# schematic_breakout_pcb.net
KiCad netlist of a schematic drawn in EAGLE
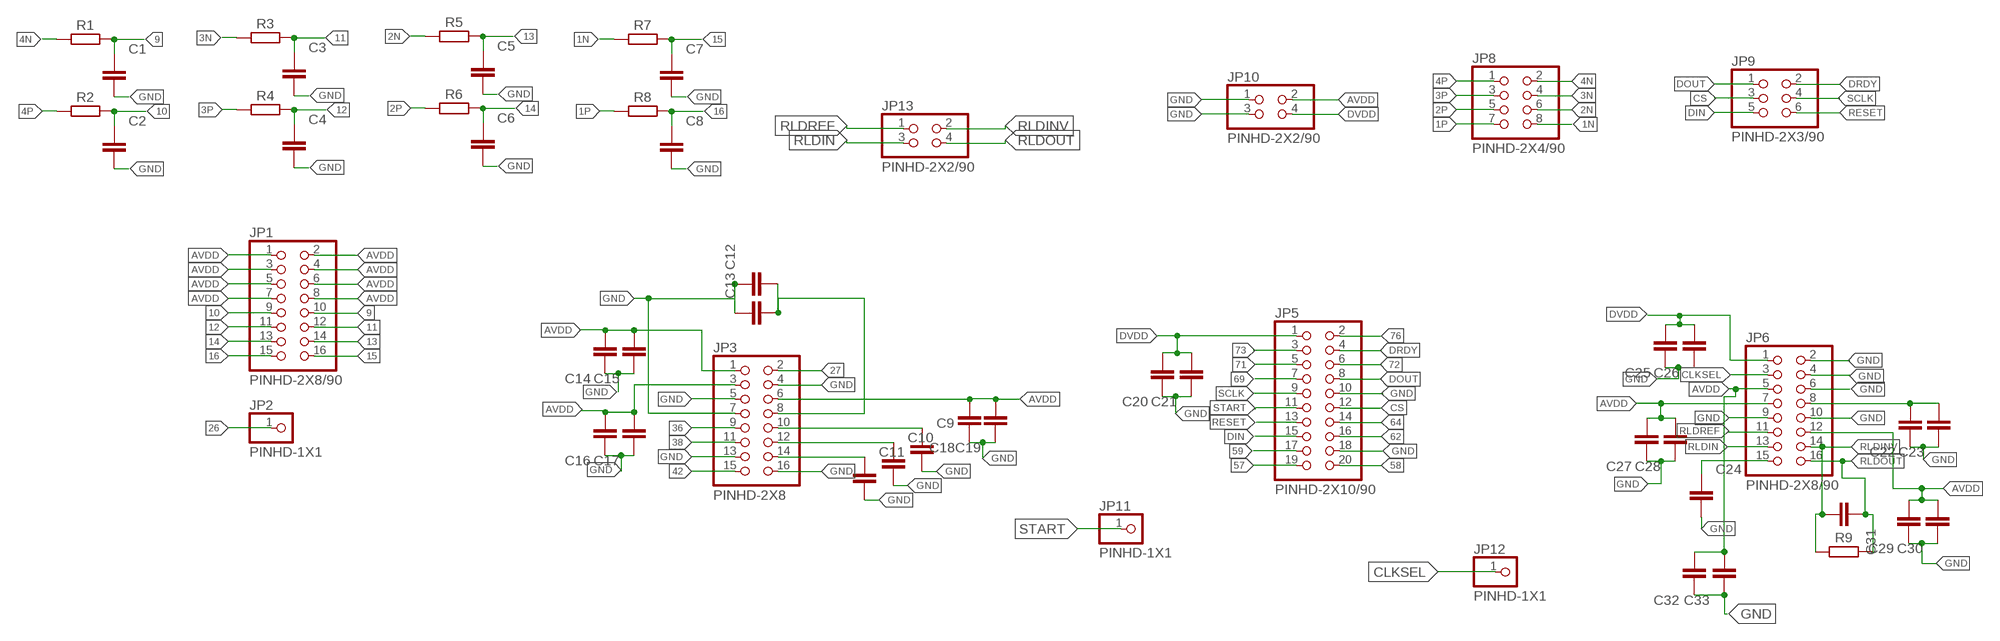
[diagram p0: schematic, sheet 1]

(export (version "E")
  (design (tool "Eeschema 10.0.6"))
  (components
    (comp (ref "C1")
      (value "C_TANTALUM-1206(3216-METRIC)")
      (footprint "eagle-import:CAPM3216X180")
      (libsource (lib "eagle-import") (part "CTANTALUM-1206(3216-METRIC)_"))
    )
    (comp (ref "C2")
      (value "C_TANTALUM-1206(3216-METRIC)")
      (footprint "eagle-import:CAPM3216X180")
      (libsource (lib "eagle-import") (part "CTANTALUM-1206(3216-METRIC)_"))
    )
    (comp (ref "C3")
      (value "C_TANTALUM-1206(3216-METRIC)")
      (footprint "eagle-import:CAPM3216X180")
      (libsource (lib "eagle-import") (part "CTANTALUM-1206(3216-METRIC)_"))
    )
    (comp (ref "C4")
      (value "C_TANTALUM-1206(3216-METRIC)")
      (footprint "eagle-import:CAPM3216X180")
      (libsource (lib "eagle-import") (part "CTANTALUM-1206(3216-METRIC)_"))
    )
    (comp (ref "C5")
      (value "C_TANTALUM-1206(3216-METRIC)")
      (footprint "eagle-import:CAPM3216X180")
      (libsource (lib "eagle-import") (part "CTANTALUM-1206(3216-METRIC)_"))
    )
    (comp (ref "C6")
      (value "C_TANTALUM-1206(3216-METRIC)")
      (footprint "eagle-import:CAPM3216X180")
      (libsource (lib "eagle-import") (part "CTANTALUM-1206(3216-METRIC)_"))
    )
    (comp (ref "C7")
      (value "C_TANTALUM-1206(3216-METRIC)")
      (footprint "eagle-import:CAPM3216X180")
      (libsource (lib "eagle-import") (part "CTANTALUM-1206(3216-METRIC)_"))
    )
    (comp (ref "C8")
      (value "C_TANTALUM-1206(3216-METRIC)")
      (footprint "eagle-import:CAPM3216X180")
      (libsource (lib "eagle-import") (part "CTANTALUM-1206(3216-METRIC)_"))
    )
    (comp (ref "C9")
      (value "C_TANTALUM-1206(3216-METRIC)")
      (footprint "eagle-import:CAPM3216X180")
      (libsource (lib "eagle-import") (part "CTANTALUM-1206(3216-METRIC)_"))
    )
    (comp (ref "C10")
      (value "C_TANTALUM-1206(3216-METRIC)")
      (footprint "eagle-import:CAPM3216X180")
      (libsource (lib "eagle-import") (part "CTANTALUM-1206(3216-METRIC)_"))
    )
    (comp (ref "C11")
      (value "C_TANTALUM-1206(3216-METRIC)")
      (footprint "eagle-import:CAPM3216X180")
      (libsource (lib "eagle-import") (part "CTANTALUM-1206(3216-METRIC)_"))
    )
    (comp (ref "C12")
      (value "C_TANTALUM-1206(3216-METRIC)")
      (footprint "eagle-import:CAPM3216X180")
      (libsource (lib "eagle-import") (part "CTANTALUM-1206(3216-METRIC)_"))
    )
    (comp (ref "C13")
      (value "C_TANTALUM-1206(3216-METRIC)")
      (footprint "eagle-import:CAPM3216X180")
      (libsource (lib "eagle-import") (part "CTANTALUM-1206(3216-METRIC)_"))
    )
    (comp (ref "C14")
      (value "C_TANTALUM-1206(3216-METRIC)")
      (footprint "eagle-import:CAPM3216X180")
      (libsource (lib "eagle-import") (part "CTANTALUM-1206(3216-METRIC)_"))
    )
    (comp (ref "C15")
      (value "C_TANTALUM-1206(3216-METRIC)")
      (footprint "eagle-import:CAPM3216X180")
      (libsource (lib "eagle-import") (part "CTANTALUM-1206(3216-METRIC)_"))
    )
    (comp (ref "C16")
      (value "C_TANTALUM-1206(3216-METRIC)")
      (footprint "eagle-import:CAPM3216X180")
      (libsource (lib "eagle-import") (part "CTANTALUM-1206(3216-METRIC)_"))
    )
    (comp (ref "C17")
      (value "C_TANTALUM-1206(3216-METRIC)")
      (footprint "eagle-import:CAPM3216X180")
      (libsource (lib "eagle-import") (part "CTANTALUM-1206(3216-METRIC)_"))
    )
    (comp (ref "C18")
      (value "C_TANTALUM-1206(3216-METRIC)")
      (footprint "eagle-import:CAPM3216X180")
      (libsource (lib "eagle-import") (part "CTANTALUM-1206(3216-METRIC)_"))
    )
    (comp (ref "C19")
      (value "C_TANTALUM-1206(3216-METRIC)")
      (footprint "eagle-import:CAPM3216X180")
      (libsource (lib "eagle-import") (part "CTANTALUM-1206(3216-METRIC)_"))
    )
    (comp (ref "C20")
      (value "C_TANTALUM-1206(3216-METRIC)")
      (footprint "eagle-import:CAPM3216X180")
      (libsource (lib "eagle-import") (part "CTANTALUM-1206(3216-METRIC)_"))
    )
    (comp (ref "C21")
      (value "C_TANTALUM-1206(3216-METRIC)")
      (footprint "eagle-import:CAPM3216X180")
      (libsource (lib "eagle-import") (part "CTANTALUM-1206(3216-METRIC)_"))
    )
    (comp (ref "C22")
      (value "C_TANTALUM-1206(3216-METRIC)")
      (footprint "eagle-import:CAPM3216X180")
      (libsource (lib "eagle-import") (part "CTANTALUM-1206(3216-METRIC)_"))
    )
    (comp (ref "C23")
      (value "C_TANTALUM-1206(3216-METRIC)")
      (footprint "eagle-import:CAPM3216X180")
      (libsource (lib "eagle-import") (part "CTANTALUM-1206(3216-METRIC)_"))
    )
    (comp (ref "C24")
      (value "C_TANTALUM-1206(3216-METRIC)")
      (footprint "eagle-import:CAPM3216X180")
      (libsource (lib "eagle-import") (part "CTANTALUM-1206(3216-METRIC)_"))
    )
    (comp (ref "C25")
      (value "C_TANTALUM-1206(3216-METRIC)")
      (footprint "eagle-import:CAPM3216X180")
      (libsource (lib "eagle-import") (part "CTANTALUM-1206(3216-METRIC)_"))
    )
    (comp (ref "C26")
      (value "C_TANTALUM-1206(3216-METRIC)")
      (footprint "eagle-import:CAPM3216X180")
      (libsource (lib "eagle-import") (part "CTANTALUM-1206(3216-METRIC)_"))
    )
    (comp (ref "C27")
      (value "C_TANTALUM-1206(3216-METRIC)")
      (footprint "eagle-import:CAPM3216X180")
      (libsource (lib "eagle-import") (part "CTANTALUM-1206(3216-METRIC)_"))
    )
    (comp (ref "C28")
      (value "C_TANTALUM-1206(3216-METRIC)")
      (footprint "eagle-import:CAPM3216X180")
      (libsource (lib "eagle-import") (part "CTANTALUM-1206(3216-METRIC)_"))
    )
    (comp (ref "C29")
      (value "C_TANTALUM-1206(3216-METRIC)")
      (footprint "eagle-import:CAPM3216X180")
      (libsource (lib "eagle-import") (part "CTANTALUM-1206(3216-METRIC)_"))
    )
    (comp (ref "C30")
      (value "C_TANTALUM-1206(3216-METRIC)")
      (footprint "eagle-import:CAPM3216X180")
      (libsource (lib "eagle-import") (part "CTANTALUM-1206(3216-METRIC)_"))
    )
    (comp (ref "C31")
      (value "C_TANTALUM-1206(3216-METRIC)")
      (footprint "eagle-import:CAPM3216X180")
      (libsource (lib "eagle-import") (part "CTANTALUM-1206(3216-METRIC)_"))
    )
    (comp (ref "C32")
      (value "C_TANTALUM-1206(3216-METRIC)")
      (footprint "eagle-import:CAPM3216X180")
      (libsource (lib "eagle-import") (part "CTANTALUM-1206(3216-METRIC)_"))
    )
    (comp (ref "C33")
      (value "C_TANTALUM-1206(3216-METRIC)")
      (footprint "eagle-import:CAPM3216X180")
      (libsource (lib "eagle-import") (part "CTANTALUM-1206(3216-METRIC)_"))
    )
    (comp (ref "JP1")
      (value "PINHD-2X8/90")
      (footprint "eagle-import:2X08_90")
      (libsource (lib "eagle-import") (part "PINHD-2X8/90"))
    )
    (comp (ref "JP2")
      (value "PINHD-1X1")
      (footprint "eagle-import:1X01")
      (libsource (lib "eagle-import") (part "PINHD-1X1"))
    )
    (comp (ref "JP3")
      (value "PINHD-2X8")
      (footprint "eagle-import:2X08")
      (libsource (lib "eagle-import") (part "PINHD-2X8"))
    )
    (comp (ref "JP5")
      (value "PINHD-2X10/90")
      (footprint "eagle-import:2X10_90")
      (libsource (lib "eagle-import") (part "PINHD-2X10/90"))
    )
    (comp (ref "JP6")
      (value "PINHD-2X8/90")
      (footprint "eagle-import:2X08_90")
      (libsource (lib "eagle-import") (part "PINHD-2X8/90"))
    )
    (comp (ref "JP8")
      (value "PINHD-2X4/90")
      (footprint "eagle-import:2X04_90")
      (libsource (lib "eagle-import") (part "PINHD-2X4/90"))
    )
    (comp (ref "JP9")
      (value "PINHD-2X3/90")
      (footprint "eagle-import:2X03_90")
      (libsource (lib "eagle-import") (part "PINHD-2X3/90"))
    )
    (comp (ref "JP10")
      (value "PINHD-2X2/90")
      (footprint "eagle-import:2X02_90")
      (libsource (lib "eagle-import") (part "PINHD-2X2/90"))
    )
    (comp (ref "JP11")
      (value "PINHD-1X1")
      (footprint "eagle-import:1X01")
      (libsource (lib "eagle-import") (part "PINHD-1X1"))
    )
    (comp (ref "JP12")
      (value "PINHD-1X1")
      (footprint "eagle-import:1X01")
      (libsource (lib "eagle-import") (part "PINHD-1X1"))
    )
    (comp (ref "JP13")
      (value "PINHD-2X2/90")
      (footprint "eagle-import:2X02_90")
      (libsource (lib "eagle-import") (part "PINHD-2X2/90"))
    )
    (comp (ref "R1")
      (value "R_CHIP-1206(3216-METRIC)")
      (footprint "eagle-import:RESC3216X70")
      (libsource (lib "eagle-import") (part "RCHIP-1206(3216-METRIC)_"))
    )
    (comp (ref "R2")
      (value "R_CHIP-1206(3216-METRIC)")
      (footprint "eagle-import:RESC3216X70")
      (libsource (lib "eagle-import") (part "RCHIP-1206(3216-METRIC)_"))
    )
    (comp (ref "R3")
      (value "R_CHIP-1206(3216-METRIC)")
      (footprint "eagle-import:RESC3216X70")
      (libsource (lib "eagle-import") (part "RCHIP-1206(3216-METRIC)_"))
    )
    (comp (ref "R4")
      (value "R_CHIP-1206(3216-METRIC)")
      (footprint "eagle-import:RESC3216X70")
      (libsource (lib "eagle-import") (part "RCHIP-1206(3216-METRIC)_"))
    )
    (comp (ref "R5")
      (value "R_CHIP-1206(3216-METRIC)")
      (footprint "eagle-import:RESC3216X70")
      (libsource (lib "eagle-import") (part "RCHIP-1206(3216-METRIC)_"))
    )
    (comp (ref "R6")
      (value "R_CHIP-1206(3216-METRIC)")
      (footprint "eagle-import:RESC3216X70")
      (libsource (lib "eagle-import") (part "RCHIP-1206(3216-METRIC)_"))
    )
    (comp (ref "R7")
      (value "R_CHIP-1206(3216-METRIC)")
      (footprint "eagle-import:RESC3216X70")
      (libsource (lib "eagle-import") (part "RCHIP-1206(3216-METRIC)_"))
    )
    (comp (ref "R8")
      (value "R_CHIP-1206(3216-METRIC)")
      (footprint "eagle-import:RESC3216X70")
      (libsource (lib "eagle-import") (part "RCHIP-1206(3216-METRIC)_"))
    )
    (comp (ref "R9")
      (value "R_CHIP-1206(3216-METRIC)")
      (footprint "eagle-import:RESC3216X70")
      (libsource (lib "eagle-import") (part "RCHIP-1206(3216-METRIC)_"))
    )
  )
  (nets
    (net (code "1") (name "1N") (class "Default")
      (node (ref "JP8") (pin "8") (pinfunction "8_8") (pintype "passive"))
      (node (ref "R7") (pin "1") (pinfunction "1_1") (pintype "passive"))
    )
    (net (code "2") (name "1P") (class "Default")
      (node (ref "JP8") (pin "7") (pinfunction "7_7") (pintype "passive"))
      (node (ref "R8") (pin "1") (pinfunction "1_1") (pintype "passive"))
    )
    (net (code "3") (name "2N") (class "Default")
      (node (ref "JP8") (pin "6") (pinfunction "6_6") (pintype "passive"))
      (node (ref "R5") (pin "1") (pinfunction "1_1") (pintype "passive"))
    )
    (net (code "4") (name "2P") (class "Default")
      (node (ref "JP8") (pin "5") (pinfunction "5_5") (pintype "passive"))
      (node (ref "R6") (pin "1") (pinfunction "1_1") (pintype "passive"))
    )
    (net (code "5") (name "3N") (class "Default")
      (node (ref "JP8") (pin "4") (pinfunction "4_4") (pintype "passive"))
      (node (ref "R3") (pin "1") (pinfunction "1_1") (pintype "passive"))
    )
    (net (code "6") (name "3P") (class "Default")
      (node (ref "JP8") (pin "3") (pinfunction "3_3") (pintype "passive"))
      (node (ref "R4") (pin "1") (pinfunction "1_1") (pintype "passive"))
    )
    (net (code "7") (name "4N") (class "Default")
      (node (ref "JP8") (pin "2") (pinfunction "2_2") (pintype "passive"))
      (node (ref "R1") (pin "1") (pinfunction "1_1") (pintype "passive"))
    )
    (net (code "8") (name "4P") (class "Default")
      (node (ref "JP8") (pin "1") (pinfunction "1_1") (pintype "passive"))
      (node (ref "R2") (pin "1") (pinfunction "1_1") (pintype "passive"))
    )
    (net (code "9") (name "9") (class "Default")
      (node (ref "C1") (pin "1") (pinfunction "1_1") (pintype "passive"))
      (node (ref "JP1") (pin "10") (pinfunction "10_10") (pintype "passive"))
      (node (ref "R1") (pin "2") (pinfunction "2_2") (pintype "passive"))
    )
    (net (code "10") (name "10") (class "Default")
      (node (ref "C2") (pin "1") (pinfunction "1_1") (pintype "passive"))
      (node (ref "JP1") (pin "9") (pinfunction "9_9") (pintype "passive"))
      (node (ref "R2") (pin "2") (pinfunction "2_2") (pintype "passive"))
    )
    (net (code "11") (name "11") (class "Default")
      (node (ref "C3") (pin "1") (pinfunction "1_1") (pintype "passive"))
      (node (ref "JP1") (pin "12") (pinfunction "12_12") (pintype "passive"))
      (node (ref "R3") (pin "2") (pinfunction "2_2") (pintype "passive"))
    )
    (net (code "12") (name "12") (class "Default")
      (node (ref "C4") (pin "1") (pinfunction "1_1") (pintype "passive"))
      (node (ref "JP1") (pin "11") (pinfunction "11_11") (pintype "passive"))
      (node (ref "R4") (pin "2") (pinfunction "2_2") (pintype "passive"))
    )
    (net (code "13") (name "13") (class "Default")
      (node (ref "C5") (pin "1") (pinfunction "1_1") (pintype "passive"))
      (node (ref "JP1") (pin "14") (pinfunction "14_14") (pintype "passive"))
      (node (ref "R5") (pin "2") (pinfunction "2_2") (pintype "passive"))
    )
    (net (code "14") (name "14") (class "Default")
      (node (ref "C6") (pin "1") (pinfunction "1_1") (pintype "passive"))
      (node (ref "JP1") (pin "13") (pinfunction "13_13") (pintype "passive"))
      (node (ref "R6") (pin "2") (pinfunction "2_2") (pintype "passive"))
    )
    (net (code "15") (name "15") (class "Default")
      (node (ref "C7") (pin "1") (pinfunction "1_1") (pintype "passive"))
      (node (ref "JP1") (pin "16") (pinfunction "16_16") (pintype "passive"))
      (node (ref "R7") (pin "2") (pinfunction "2_2") (pintype "passive"))
    )
    (net (code "16") (name "16") (class "Default")
      (node (ref "C8") (pin "1") (pinfunction "1_1") (pintype "passive"))
      (node (ref "JP1") (pin "15") (pinfunction "15_15") (pintype "passive"))
      (node (ref "R8") (pin "2") (pinfunction "2_2") (pintype "passive"))
    )
    (net (code "17") (name "26") (class "Default")
      (node (ref "JP2") (pin "1") (pinfunction "1_1") (pintype "passive"))
    )
    (net (code "18") (name "27") (class "Default")
      (node (ref "JP3") (pin "2") (pinfunction "2_2") (pintype "passive"))
    )
    (net (code "19") (name "36") (class "Default")
      (node (ref "JP3") (pin "9") (pinfunction "9_9") (pintype "passive"))
    )
    (net (code "20") (name "38") (class "Default")
      (node (ref "JP3") (pin "11") (pinfunction "11_11") (pintype "passive"))
    )
    (net (code "21") (name "42") (class "Default")
      (node (ref "JP3") (pin "15") (pinfunction "15_15") (pintype "passive"))
    )
    (net (code "22") (name "57") (class "Default")
      (node (ref "JP5") (pin "19") (pinfunction "19_19") (pintype "passive"))
    )
    (net (code "23") (name "58") (class "Default")
      (node (ref "JP5") (pin "20") (pinfunction "20_20") (pintype "passive"))
    )
    (net (code "24") (name "59") (class "Default")
      (node (ref "JP5") (pin "17") (pinfunction "17_17") (pintype "passive"))
    )
    (net (code "25") (name "62") (class "Default")
      (node (ref "JP5") (pin "16") (pinfunction "16_16") (pintype "passive"))
    )
    (net (code "26") (name "64") (class "Default")
      (node (ref "JP5") (pin "14") (pinfunction "14_14") (pintype "passive"))
    )
    (net (code "27") (name "69") (class "Default")
      (node (ref "JP5") (pin "7") (pinfunction "7_7") (pintype "passive"))
    )
    (net (code "28") (name "71") (class "Default")
      (node (ref "JP5") (pin "5") (pinfunction "5_5") (pintype "passive"))
    )
    (net (code "29") (name "72") (class "Default")
      (node (ref "JP5") (pin "6") (pinfunction "6_6") (pintype "passive"))
    )
    (net (code "30") (name "73") (class "Default")
      (node (ref "JP5") (pin "3") (pinfunction "3_3") (pintype "passive"))
    )
    (net (code "31") (name "76") (class "Default")
      (node (ref "JP5") (pin "2") (pinfunction "2_2") (pintype "passive"))
    )
    (net (code "32") (name "AVDD") (class "Default")
      (node (ref "C14") (pin "2") (pinfunction "2_2") (pintype "passive"))
      (node (ref "C15") (pin "2") (pinfunction "2_2") (pintype "passive"))
      (node (ref "C16") (pin "2") (pinfunction "2_2") (pintype "passive"))
      (node (ref "C17") (pin "2") (pinfunction "2_2") (pintype "passive"))
      (node (ref "C18") (pin "2") (pinfunction "2_2") (pintype "passive"))
      (node (ref "C19") (pin "2") (pinfunction "2_2") (pintype "passive"))
      (node (ref "C27") (pin "2") (pinfunction "2_2") (pintype "passive"))
      (node (ref "C28") (pin "2") (pinfunction "2_2") (pintype "passive"))
      (node (ref "C29") (pin "2") (pinfunction "2_2") (pintype "passive"))
      (node (ref "C30") (pin "2") (pinfunction "2_2") (pintype "passive"))
      (node (ref "C32") (pin "2") (pinfunction "2_2") (pintype "passive"))
      (node (ref "C33") (pin "2") (pinfunction "2_2") (pintype "passive"))
      (node (ref "JP1") (pin "1") (pinfunction "1_1") (pintype "passive"))
      (node (ref "JP1") (pin "2") (pinfunction "2_2") (pintype "passive"))
      (node (ref "JP1") (pin "3") (pinfunction "3_3") (pintype "passive"))
      (node (ref "JP1") (pin "4") (pinfunction "4_4") (pintype "passive"))
      (node (ref "JP1") (pin "5") (pinfunction "5_5") (pintype "passive"))
      (node (ref "JP1") (pin "6") (pinfunction "6_6") (pintype "passive"))
      (node (ref "JP1") (pin "7") (pinfunction "7_7") (pintype "passive"))
      (node (ref "JP1") (pin "8") (pinfunction "8_8") (pintype "passive"))
      (node (ref "JP10") (pin "2") (pinfunction "2_2") (pintype "passive"))
      (node (ref "JP3") (pin "1") (pinfunction "1_1") (pintype "passive"))
      (node (ref "JP3") (pin "3") (pinfunction "3_3") (pintype "passive"))
      (node (ref "JP3") (pin "6") (pinfunction "6_6") (pintype "passive"))
      (node (ref "JP6") (pin "12") (pinfunction "12_12") (pintype "passive"))
      (node (ref "JP6") (pin "5") (pinfunction "5_5") (pintype "passive"))
      (node (ref "JP6") (pin "7") (pinfunction "7_7") (pintype "passive"))
    )
    (net (code "33") (name "CLKSEL") (class "Default")
      (node (ref "JP12") (pin "1") (pinfunction "1_1") (pintype "passive"))
      (node (ref "JP6") (pin "3") (pinfunction "3_3") (pintype "passive"))
    )
    (net (code "34") (name "CS") (class "Default")
      (node (ref "JP5") (pin "12") (pinfunction "12_12") (pintype "passive"))
      (node (ref "JP9") (pin "3") (pinfunction "3_3") (pintype "passive"))
    )
    (net (code "35") (name "DIN") (class "Default")
      (node (ref "JP5") (pin "15") (pinfunction "15_15") (pintype "passive"))
      (node (ref "JP9") (pin "5") (pinfunction "5_5") (pintype "passive"))
    )
    (net (code "36") (name "DOUT") (class "Default")
      (node (ref "JP5") (pin "8") (pinfunction "8_8") (pintype "passive"))
      (node (ref "JP9") (pin "1") (pinfunction "1_1") (pintype "passive"))
    )
    (net (code "37") (name "DRDY") (class "Default")
      (node (ref "JP5") (pin "4") (pinfunction "4_4") (pintype "passive"))
      (node (ref "JP9") (pin "2") (pinfunction "2_2") (pintype "passive"))
    )
    (net (code "38") (name "DVDD") (class "Default")
      (node (ref "C20") (pin "2") (pinfunction "2_2") (pintype "passive"))
      (node (ref "C21") (pin "2") (pinfunction "2_2") (pintype "passive"))
      (node (ref "C25") (pin "2") (pinfunction "2_2") (pintype "passive"))
      (node (ref "C26") (pin "2") (pinfunction "2_2") (pintype "passive"))
      (node (ref "JP10") (pin "4") (pinfunction "4_4") (pintype "passive"))
      (node (ref "JP5") (pin "1") (pinfunction "1_1") (pintype "passive"))
      (node (ref "JP6") (pin "1") (pinfunction "1_1") (pintype "passive"))
    )
    (net (code "39") (name "GND") (class "Default")
      (node (ref "C1") (pin "2") (pinfunction "2_2") (pintype "passive"))
      (node (ref "C10") (pin "2") (pinfunction "2_2") (pintype "passive"))
      (node (ref "C11") (pin "2") (pinfunction "2_2") (pintype "passive"))
      (node (ref "C12") (pin "1") (pinfunction "1_1") (pintype "passive"))
      (node (ref "C13") (pin "1") (pinfunction "1_1") (pintype "passive"))
      (node (ref "C14") (pin "1") (pinfunction "1_1") (pintype "passive"))
      (node (ref "C15") (pin "1") (pinfunction "1_1") (pintype "passive"))
      (node (ref "C16") (pin "1") (pinfunction "1_1") (pintype "passive"))
      (node (ref "C17") (pin "1") (pinfunction "1_1") (pintype "passive"))
      (node (ref "C18") (pin "1") (pinfunction "1_1") (pintype "passive"))
      (node (ref "C19") (pin "1") (pinfunction "1_1") (pintype "passive"))
      (node (ref "C2") (pin "2") (pinfunction "2_2") (pintype "passive"))
      (node (ref "C20") (pin "1") (pinfunction "1_1") (pintype "passive"))
      (node (ref "C21") (pin "1") (pinfunction "1_1") (pintype "passive"))
      (node (ref "C22") (pin "1") (pinfunction "1_1") (pintype "passive"))
      (node (ref "C23") (pin "1") (pinfunction "1_1") (pintype "passive"))
      (node (ref "C24") (pin "2") (pinfunction "2_2") (pintype "passive"))
      (node (ref "C25") (pin "1") (pinfunction "1_1") (pintype "passive"))
      (node (ref "C26") (pin "1") (pinfunction "1_1") (pintype "passive"))
      (node (ref "C27") (pin "1") (pinfunction "1_1") (pintype "passive"))
      (node (ref "C28") (pin "1") (pinfunction "1_1") (pintype "passive"))
      (node (ref "C29") (pin "1") (pinfunction "1_1") (pintype "passive"))
      (node (ref "C3") (pin "2") (pinfunction "2_2") (pintype "passive"))
      (node (ref "C30") (pin "1") (pinfunction "1_1") (pintype "passive"))
      (node (ref "C32") (pin "1") (pinfunction "1_1") (pintype "passive"))
      (node (ref "C33") (pin "1") (pinfunction "1_1") (pintype "passive"))
      (node (ref "C4") (pin "2") (pinfunction "2_2") (pintype "passive"))
      (node (ref "C5") (pin "2") (pinfunction "2_2") (pintype "passive"))
      (node (ref "C6") (pin "2") (pinfunction "2_2") (pintype "passive"))
      (node (ref "C7") (pin "2") (pinfunction "2_2") (pintype "passive"))
      (node (ref "C8") (pin "2") (pinfunction "2_2") (pintype "passive"))
      (node (ref "C9") (pin "2") (pinfunction "2_2") (pintype "passive"))
      (node (ref "JP10") (pin "1") (pinfunction "1_1") (pintype "passive"))
      (node (ref "JP10") (pin "3") (pinfunction "3_3") (pintype "passive"))
      (node (ref "JP3") (pin "13") (pinfunction "13_13") (pintype "passive"))
      (node (ref "JP3") (pin "16") (pinfunction "16_16") (pintype "passive"))
      (node (ref "JP3") (pin "4") (pinfunction "4_4") (pintype "passive"))
      (node (ref "JP3") (pin "5") (pinfunction "5_5") (pintype "passive"))
      (node (ref "JP3") (pin "7") (pinfunction "7_7") (pintype "passive"))
      (node (ref "JP5") (pin "10") (pinfunction "10_10") (pintype "passive"))
      (node (ref "JP5") (pin "18") (pinfunction "18_18") (pintype "passive"))
      (node (ref "JP6") (pin "10") (pinfunction "10_10") (pintype "passive"))
      (node (ref "JP6") (pin "2") (pinfunction "2_2") (pintype "passive"))
      (node (ref "JP6") (pin "4") (pinfunction "4_4") (pintype "passive"))
      (node (ref "JP6") (pin "6") (pinfunction "6_6") (pintype "passive"))
      (node (ref "JP6") (pin "9") (pinfunction "9_9") (pintype "passive"))
    )
    (net (code "40") (name "Net-(C9-Pad1)") (class "Default")
      (node (ref "C9") (pin "1") (pinfunction "1_1") (pintype "passive"))
      (node (ref "JP3") (pin "10") (pinfunction "10_10") (pintype "passive"))
    )
    (net (code "41") (name "Net-(C10-Pad1)") (class "Default")
      (node (ref "C10") (pin "1") (pinfunction "1_1") (pintype "passive"))
      (node (ref "JP3") (pin "12") (pinfunction "12_12") (pintype "passive"))
    )
    (net (code "42") (name "Net-(C11-Pad1)") (class "Default")
      (node (ref "C11") (pin "1") (pinfunction "1_1") (pintype "passive"))
      (node (ref "JP3") (pin "14") (pinfunction "14_14") (pintype "passive"))
    )
    (net (code "43") (name "Net-(C12-Pad2)") (class "Default")
      (node (ref "C12") (pin "2") (pinfunction "2_2") (pintype "passive"))
      (node (ref "C13") (pin "2") (pinfunction "2_2") (pintype "passive"))
      (node (ref "JP3") (pin "8") (pinfunction "8_8") (pintype "passive"))
    )
    (net (code "44") (name "Net-(C22-Pad2)") (class "Default")
      (node (ref "C22") (pin "2") (pinfunction "2_2") (pintype "passive"))
      (node (ref "C23") (pin "2") (pinfunction "2_2") (pintype "passive"))
      (node (ref "JP6") (pin "8") (pinfunction "8_8") (pintype "passive"))
    )
    (net (code "45") (name "Net-(C24-Pad1)") (class "Default")
      (node (ref "C24") (pin "1") (pinfunction "1_1") (pintype "passive"))
      (node (ref "JP6") (pin "15") (pinfunction "15_15") (pintype "passive"))
    )
    (net (code "46") (name "RESET") (class "Default")
      (node (ref "JP5") (pin "13") (pinfunction "13_13") (pintype "passive"))
      (node (ref "JP9") (pin "6") (pinfunction "6_6") (pintype "passive"))
    )
    (net (code "47") (name "RLDIN") (class "Default")
      (node (ref "JP13") (pin "3") (pinfunction "3_3") (pintype "passive"))
      (node (ref "JP6") (pin "13") (pinfunction "13_13") (pintype "passive"))
    )
    (net (code "48") (name "RLDINV") (class "Default")
      (node (ref "C31") (pin "2") (pinfunction "2_2") (pintype "passive"))
      (node (ref "JP13") (pin "2") (pinfunction "2_2") (pintype "passive"))
      (node (ref "JP6") (pin "14") (pinfunction "14_14") (pintype "passive"))
      (node (ref "R9") (pin "1") (pinfunction "1_1") (pintype "passive"))
    )
    (net (code "49") (name "RLDOUT") (class "Default")
      (node (ref "C31") (pin "1") (pinfunction "1_1") (pintype "passive"))
      (node (ref "JP13") (pin "4") (pinfunction "4_4") (pintype "passive"))
      (node (ref "JP6") (pin "16") (pinfunction "16_16") (pintype "passive"))
      (node (ref "R9") (pin "2") (pinfunction "2_2") (pintype "passive"))
    )
    (net (code "50") (name "RLDREF") (class "Default")
      (node (ref "JP13") (pin "1") (pinfunction "1_1") (pintype "passive"))
      (node (ref "JP6") (pin "11") (pinfunction "11_11") (pintype "passive"))
    )
    (net (code "51") (name "SCLK") (class "Default")
      (node (ref "JP5") (pin "9") (pinfunction "9_9") (pintype "passive"))
      (node (ref "JP9") (pin "4") (pinfunction "4_4") (pintype "passive"))
    )
    (net (code "52") (name "START") (class "Default")
      (node (ref "JP11") (pin "1") (pinfunction "1_1") (pintype "passive"))
      (node (ref "JP5") (pin "11") (pinfunction "11_11") (pintype "passive"))
    )
  )
)
